# USB_Hub.net
KiCad netlist of a schematic drawn in Altium Designer
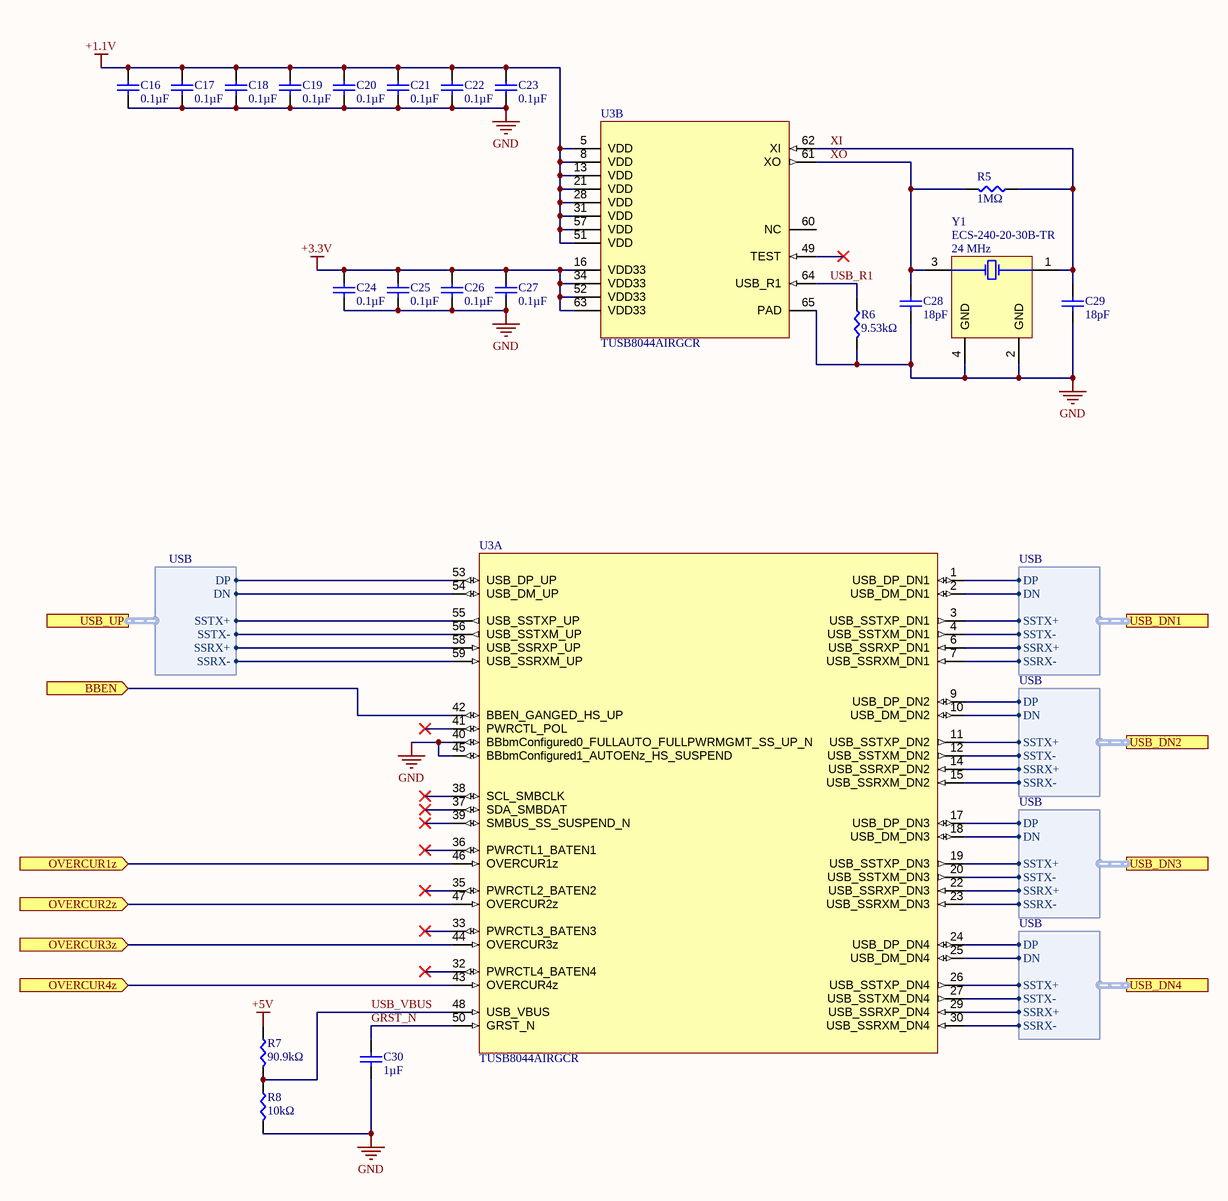
[diagram p0: USB_Hub.SchDoc]

(export (version "E")
  (design (tool "Eeschema 10.0.6"))
  (components
    (comp (ref "C16")
      (value "0.1µF")
      (footprint "CAP0402")
      (description "0.1 µF ±10% 50V Ceramic Capacitor X5R 0402 (1005 Metric)")
      (fields (field (name "VOLTAGE") "50V") (field (name "Comment") "CC0402KRX5R9BB104"))
      (libsource (lib "Schlib1") (part "CC0402KRX5R9BB104"))
    )
    (comp (ref "C17")
      (value "0.1µF")
      (footprint "CAP0402")
      (description "0.1 µF ±10% 50V Ceramic Capacitor X5R 0402 (1005 Metric)")
      (fields (field (name "VOLTAGE") "50V") (field (name "Comment") "CC0402KRX5R9BB104"))
      (libsource (lib "Schlib1") (part "CC0402KRX5R9BB104"))
    )
    (comp (ref "C18")
      (value "0.1µF")
      (footprint "CAP0402")
      (description "0.1 µF ±10% 50V Ceramic Capacitor X5R 0402 (1005 Metric)")
      (fields (field (name "VOLTAGE") "50V") (field (name "Comment") "CC0402KRX5R9BB104"))
      (libsource (lib "Schlib1") (part "CC0402KRX5R9BB104"))
    )
    (comp (ref "C19")
      (value "0.1µF")
      (footprint "CAP0402")
      (description "0.1 µF ±10% 50V Ceramic Capacitor X5R 0402 (1005 Metric)")
      (fields (field (name "VOLTAGE") "50V") (field (name "Comment") "CC0402KRX5R9BB104"))
      (libsource (lib "Schlib1") (part "CC0402KRX5R9BB104"))
    )
    (comp (ref "C20")
      (value "0.1µF")
      (footprint "CAP0402")
      (description "0.1 µF ±10% 50V Ceramic Capacitor X5R 0402 (1005 Metric)")
      (fields (field (name "VOLTAGE") "50V") (field (name "Comment") "CC0402KRX5R9BB104"))
      (libsource (lib "Schlib1") (part "CC0402KRX5R9BB104"))
    )
    (comp (ref "C21")
      (value "0.1µF")
      (footprint "CAP0402")
      (description "0.1 µF ±10% 50V Ceramic Capacitor X5R 0402 (1005 Metric)")
      (fields (field (name "VOLTAGE") "50V") (field (name "Comment") "CC0402KRX5R9BB104"))
      (libsource (lib "Schlib1") (part "CC0402KRX5R9BB104"))
    )
    (comp (ref "C22")
      (value "0.1µF")
      (footprint "CAP0402")
      (description "0.1 µF ±10% 50V Ceramic Capacitor X5R 0402 (1005 Metric)")
      (fields (field (name "VOLTAGE") "50V") (field (name "Comment") "CC0402KRX5R9BB104"))
      (libsource (lib "Schlib1") (part "CC0402KRX5R9BB104"))
    )
    (comp (ref "C23")
      (value "0.1µF")
      (footprint "CAP0402")
      (description "0.1 µF ±10% 50V Ceramic Capacitor X5R 0402 (1005 Metric)")
      (fields (field (name "VOLTAGE") "50V") (field (name "Comment") "CC0402KRX5R9BB104"))
      (libsource (lib "Schlib1") (part "CC0402KRX5R9BB104"))
    )
    (comp (ref "C24")
      (value "0.1µF")
      (footprint "CAP0402")
      (description "0.1 µF ±10% 50V Ceramic Capacitor X5R 0402 (1005 Metric)")
      (fields (field (name "VOLTAGE") "50V") (field (name "Comment") "CC0402KRX5R9BB104"))
      (libsource (lib "Schlib1") (part "CC0402KRX5R9BB104"))
    )
    (comp (ref "C25")
      (value "0.1µF")
      (footprint "CAP0402")
      (description "0.1 µF ±10% 50V Ceramic Capacitor X5R 0402 (1005 Metric)")
      (fields (field (name "VOLTAGE") "50V") (field (name "Comment") "CC0402KRX5R9BB104"))
      (libsource (lib "Schlib1") (part "CC0402KRX5R9BB104"))
    )
    (comp (ref "C26")
      (value "0.1µF")
      (footprint "CAP0402")
      (description "0.1 µF ±10% 50V Ceramic Capacitor X5R 0402 (1005 Metric)")
      (fields (field (name "VOLTAGE") "50V") (field (name "Comment") "CC0402KRX5R9BB104"))
      (libsource (lib "Schlib1") (part "CC0402KRX5R9BB104"))
    )
    (comp (ref "C27")
      (value "0.1µF")
      (footprint "CAP0402")
      (description "0.1 µF ±10% 50V Ceramic Capacitor X5R 0402 (1005 Metric)")
      (fields (field (name "VOLTAGE") "50V") (field (name "Comment") "CC0402KRX5R9BB104"))
      (libsource (lib "Schlib1") (part "CC0402KRX5R9BB104"))
    )
    (comp (ref "C28")
      (value "18pF")
      (footprint "CAP0402")
      (description "18 pF ±1% 50V Ceramic Capacitor C0G, NP0 0402 (1005 Metric)")
      (fields (field (name "VOLTAGE") "50V") (field (name "Comment") "GJM1555C1H180FB01D"))
      (libsource (lib "Schlib1") (part "GJM1555C1H180FB01D"))
    )
    (comp (ref "C29")
      (value "18pF")
      (footprint "CAP0402")
      (description "18 pF ±1% 50V Ceramic Capacitor C0G, NP0 0402 (1005 Metric)")
      (fields (field (name "VOLTAGE") "50V") (field (name "Comment") "GJM1555C1H180FB01D"))
      (libsource (lib "Schlib1") (part "GJM1555C1H180FB01D"))
    )
    (comp (ref "C30")
      (value "1µF")
      (footprint "CAP0402")
      (description "1 µF ±10% 50V Ceramic Capacitor X5R 0402 (1005 Metric)")
      (fields (field (name "VOLTAGE") "50V") (field (name "Comment") "GRM155R61H105KE05D"))
      (libsource (lib "Schlib1") (part "GRM155R61H105KE05D"))
    )
    (comp (ref "R5")
      (value "1MΩ")
      (footprint "RES0402")
      (description "1 MOhms ±1% 0.063W, 1/16W Chip Resistor 0402 (1005 Metric) Moisture Resistant Thick Film")
      (fields (field (name "Comment") "RC0402FR-071ML"))
      (libsource (lib "Schlib1") (part "RC0402FR-071ML"))
    )
    (comp (ref "R6")
      (value "9.53kΩ")
      (footprint "RES0402")
      (description "9.53 kOhms ±1% 0.1W, 1/10W Chip Resistor 0402 (1005 Metric) Automotive AEC-Q200 Thick Film")
      (fields (field (name "Comment") "CRCW04029K53FKED"))
      (libsource (lib "Schlib1") (part "CRCW04029K53FKED"))
    )
    (comp (ref "R7")
      (value "90.9kΩ")
      (footprint "RES0402")
      (description "90.9 kOhms ±1% 0.063W, 1/16W Chip Resistor 0402 (1005 Metric) Moisture Resistant Thick Film")
      (fields (field (name "Comment") "RC0402FR-0790K9L"))
      (libsource (lib "Schlib1") (part "RC0402FR-0790K9L"))
    )
    (comp (ref "R8")
      (value "10kΩ")
      (footprint "RES0402")
      (description "10 kOhms ±1% 0.063W, 1/16W Chip Resistor 0402 (1005 Metric) Moisture Resistant Thick Film")
      (fields (field (name "Comment") "RC0402FR-0710KL"))
      (libsource (lib "Schlib1") (part "RC0402FR-0710KL"))
    )
    (comp (ref "U3")
      (value "TUSB8044AIRGCR")
      (footprint "RGC0064G")
      (description "Four-port USB 3.2 x1 Gen1 hub with USB billboard 64-VQFN -40 to 85")
      (fields (field (name "COPYRIGHT") "Copyright (C) 2026 Ultra Librarian. All rights reserved."))
      (libsource (lib "Schlib1") (part "TUSB8044AIRGCR"))
    )
    (comp (ref "Y1")
      (value "ECS-240-20-30B-TR")
      (footprint "ECS-240-20-30B-TR")
      (description "24 MHz ±30ppm Crystal 20pF 30 Ohms 4-SMD, No Lead")
      (fields (field (name "ALTIUM_VALUE") "24 MHz"))
      (libsource (lib "Schlib1") (part "ECS-240-20-30B-TR"))
    )
  )
  (nets
    (net (code "2") (name "+1.1V") (class "Default")
      (node (ref "C16") (pin "2") (pinfunction "2_2") (pintype "passive"))
      (node (ref "C17") (pin "2") (pinfunction "2_2") (pintype "passive"))
      (node (ref "C18") (pin "2") (pinfunction "2_2") (pintype "passive"))
      (node (ref "C19") (pin "2") (pinfunction "2_2") (pintype "passive"))
      (node (ref "C20") (pin "2") (pinfunction "2_2") (pintype "passive"))
      (node (ref "C21") (pin "2") (pinfunction "2_2") (pintype "passive"))
      (node (ref "C22") (pin "2") (pinfunction "2_2") (pintype "passive"))
      (node (ref "C23") (pin "2") (pinfunction "2_2") (pintype "passive"))
      (node (ref "U3") (pin "13") (pinfunction "VDD_13") (pintype "power_in"))
      (node (ref "U3") (pin "21") (pinfunction "VDD_21") (pintype "power_in"))
      (node (ref "U3") (pin "28") (pinfunction "VDD_28") (pintype "power_in"))
      (node (ref "U3") (pin "31") (pinfunction "VDD_31") (pintype "power_in"))
      (node (ref "U3") (pin "5") (pinfunction "VDD_5") (pintype "power_in"))
      (node (ref "U3") (pin "51") (pinfunction "VDD_51") (pintype "power_in"))
      (node (ref "U3") (pin "57") (pinfunction "VDD_57") (pintype "power_in"))
      (node (ref "U3") (pin "8") (pinfunction "VDD_8") (pintype "power_in"))
    )
    (net (code "3") (name "+3.3V") (class "Default")
      (node (ref "C24") (pin "2") (pinfunction "2_2") (pintype "passive"))
      (node (ref "C25") (pin "2") (pinfunction "2_2") (pintype "passive"))
      (node (ref "C26") (pin "2") (pinfunction "2_2") (pintype "passive"))
      (node (ref "C27") (pin "2") (pinfunction "2_2") (pintype "passive"))
      (node (ref "U3") (pin "16") (pinfunction "VDD33_16") (pintype "power_in"))
      (node (ref "U3") (pin "34") (pinfunction "VDD33_34") (pintype "power_in"))
      (node (ref "U3") (pin "52") (pinfunction "VDD33_52") (pintype "power_in"))
      (node (ref "U3") (pin "63") (pinfunction "VDD33_63") (pintype "power_in"))
    )
    (net (code "4") (name "+5V") (class "Default")
      (node (ref "R7") (pin "2") (pinfunction "2_2") (pintype "passive"))
    )
    (net (code "5") (name "/BBEN") (class "Default")
      (node (ref "U3") (pin "42") (pinfunction "BBEN_GANGED_HS_UP_42") (pintype "bidirectional"))
    )
    (net (code "6") (name "/GRST_N") (class "Default")
      (node (ref "C30") (pin "2") (pinfunction "2_2") (pintype "passive"))
      (node (ref "U3") (pin "50") (pinfunction "GRST_N_50") (pintype "input"))
    )
    (net (code "7") (name "/OVERCUR1z") (class "Default")
      (node (ref "U3") (pin "46") (pinfunction "OVERCUR1z_46") (pintype "input"))
    )
    (net (code "8") (name "/OVERCUR2z") (class "Default")
      (node (ref "U3") (pin "47") (pinfunction "OVERCUR2z_47") (pintype "input"))
    )
    (net (code "9") (name "/OVERCUR3z") (class "Default")
      (node (ref "U3") (pin "44") (pinfunction "OVERCUR3z_44") (pintype "input"))
    )
    (net (code "10") (name "/OVERCUR4z") (class "Default")
      (node (ref "U3") (pin "43") (pinfunction "OVERCUR4z_43") (pintype "input"))
    )
    (net (code "11") (name "/USB_R1") (class "Default")
      (node (ref "R6") (pin "2") (pinfunction "2_2") (pintype "passive"))
      (node (ref "U3") (pin "64") (pinfunction "USB_R1_64") (pintype "input"))
    )
    (net (code "12") (name "/USB_VBUS") (class "Default")
      (node (ref "R7") (pin "1") (pinfunction "1_1") (pintype "passive"))
      (node (ref "R8") (pin "2") (pinfunction "2_2") (pintype "passive"))
      (node (ref "U3") (pin "48") (pinfunction "USB_VBUS_48") (pintype "input"))
    )
    (net (code "13") (name "/XI") (class "Default")
      (node (ref "C29") (pin "2") (pinfunction "2_2") (pintype "passive"))
      (node (ref "R5") (pin "2") (pinfunction "2_2") (pintype "passive"))
      (node (ref "U3") (pin "62") (pinfunction "XI_62") (pintype "input"))
      (node (ref "Y1") (pin "1") (pintype "passive"))
    )
    (net (code "14") (name "/XO") (class "Default")
      (node (ref "C28") (pin "2") (pinfunction "2_2") (pintype "passive"))
      (node (ref "R5") (pin "1") (pinfunction "1_1") (pintype "passive"))
      (node (ref "U3") (pin "61") (pinfunction "XO_61") (pintype "output"))
      (node (ref "Y1") (pin "3") (pintype "passive"))
    )
    (net (code "16") (name "GND") (class "Default")
      (node (ref "C16") (pin "1") (pinfunction "1_1") (pintype "passive"))
      (node (ref "C17") (pin "1") (pinfunction "1_1") (pintype "passive"))
      (node (ref "C18") (pin "1") (pinfunction "1_1") (pintype "passive"))
      (node (ref "C19") (pin "1") (pinfunction "1_1") (pintype "passive"))
      (node (ref "C20") (pin "1") (pinfunction "1_1") (pintype "passive"))
      (node (ref "C21") (pin "1") (pinfunction "1_1") (pintype "passive"))
      (node (ref "C22") (pin "1") (pinfunction "1_1") (pintype "passive"))
      (node (ref "C23") (pin "1") (pinfunction "1_1") (pintype "passive"))
      (node (ref "C24") (pin "1") (pinfunction "1_1") (pintype "passive"))
      (node (ref "C25") (pin "1") (pinfunction "1_1") (pintype "passive"))
      (node (ref "C26") (pin "1") (pinfunction "1_1") (pintype "passive"))
      (node (ref "C27") (pin "1") (pinfunction "1_1") (pintype "passive"))
      (node (ref "C28") (pin "1") (pinfunction "1_1") (pintype "passive"))
      (node (ref "C29") (pin "1") (pinfunction "1_1") (pintype "passive"))
      (node (ref "C30") (pin "1") (pinfunction "1_1") (pintype "passive"))
      (node (ref "R6") (pin "1") (pinfunction "1_1") (pintype "passive"))
      (node (ref "R8") (pin "1") (pinfunction "1_1") (pintype "passive"))
      (node (ref "U3") (pin "40") (pinfunction "BBbmConfigured0_FULLAUTO_FULLPWRMGMT_SS_UP_N_40") (pintype "bidirectional"))
      (node (ref "U3") (pin "45") (pinfunction "BBbmConfigured1_AUTOENz_HS_SUSPEND_45") (pintype "bidirectional"))
      (node (ref "U3") (pin "65") (pinfunction "PAD_65") (pintype "passive"))
      (node (ref "Y1") (pin "2") (pinfunction "GND_2") (pintype "passive"))
      (node (ref "Y1") (pin "4") (pinfunction "GND_4") (pintype "passive"))
    )
    (net (code "17") (name "unconnected-(U3A-PWRCTL1_BATEN1-Pad36)") (class "Default")
      (node (ref "U3") (pin "36") (pinfunction "PWRCTL1_BATEN1_36") (pintype "bidirectional+no_connect"))
    )
    (net (code "18") (name "unconnected-(U3A-PWRCTL2_BATEN2-Pad35)") (class "Default")
      (node (ref "U3") (pin "35") (pinfunction "PWRCTL2_BATEN2_35") (pintype "bidirectional+no_connect"))
    )
    (net (code "19") (name "unconnected-(U3A-PWRCTL3_BATEN3-Pad33)") (class "Default")
      (node (ref "U3") (pin "33") (pinfunction "PWRCTL3_BATEN3_33") (pintype "bidirectional+no_connect"))
    )
    (net (code "20") (name "unconnected-(U3A-PWRCTL4_BATEN4-Pad32)") (class "Default")
      (node (ref "U3") (pin "32") (pinfunction "PWRCTL4_BATEN4_32") (pintype "bidirectional+no_connect"))
    )
    (net (code "21") (name "unconnected-(U3A-PWRCTL_POL-Pad41)") (class "Default")
      (node (ref "U3") (pin "41") (pinfunction "PWRCTL_POL_41") (pintype "bidirectional+no_connect"))
    )
    (net (code "22") (name "unconnected-(U3A-SCL_SMBCLK-Pad38)") (class "Default")
      (node (ref "U3") (pin "38") (pinfunction "SCL_SMBCLK_38") (pintype "bidirectional+no_connect"))
    )
    (net (code "23") (name "unconnected-(U3A-SDA_SMBDAT-Pad37)") (class "Default")
      (node (ref "U3") (pin "37") (pinfunction "SDA_SMBDAT_37") (pintype "bidirectional+no_connect"))
    )
    (net (code "24") (name "unconnected-(U3A-SMBUS_SS_SUSPEND_N-Pad39)") (class "Default")
      (node (ref "U3") (pin "39") (pinfunction "SMBUS_SS_SUSPEND_N_39") (pintype "bidirectional+no_connect"))
    )
    (net (code "25") (name "unconnected-(U3A-USB_DM_DN1-Pad2)") (class "Default")
      (node (ref "U3") (pin "2") (pinfunction "USB_DM_DN1_2") (pintype "bidirectional"))
    )
    (net (code "26") (name "unconnected-(U3A-USB_DM_DN2-Pad10)") (class "Default")
      (node (ref "U3") (pin "10") (pinfunction "USB_DM_DN2_10") (pintype "bidirectional"))
    )
    (net (code "27") (name "unconnected-(U3A-USB_DM_DN3-Pad18)") (class "Default")
      (node (ref "U3") (pin "18") (pinfunction "USB_DM_DN3_18") (pintype "bidirectional"))
    )
    (net (code "28") (name "unconnected-(U3A-USB_DM_DN4-Pad25)") (class "Default")
      (node (ref "U3") (pin "25") (pinfunction "USB_DM_DN4_25") (pintype "bidirectional"))
    )
    (net (code "29") (name "unconnected-(U3A-USB_DM_UP-Pad54)") (class "Default")
      (node (ref "U3") (pin "54") (pinfunction "USB_DM_UP_54") (pintype "bidirectional"))
    )
    (net (code "30") (name "unconnected-(U3A-USB_DP_DN1-Pad1)") (class "Default")
      (node (ref "U3") (pin "1") (pinfunction "USB_DP_DN1_1") (pintype "bidirectional"))
    )
    (net (code "31") (name "unconnected-(U3A-USB_DP_DN2-Pad9)") (class "Default")
      (node (ref "U3") (pin "9") (pinfunction "USB_DP_DN2_9") (pintype "bidirectional"))
    )
    (net (code "32") (name "unconnected-(U3A-USB_DP_DN3-Pad17)") (class "Default")
      (node (ref "U3") (pin "17") (pinfunction "USB_DP_DN3_17") (pintype "bidirectional"))
    )
    (net (code "33") (name "unconnected-(U3A-USB_DP_DN4-Pad24)") (class "Default")
      (node (ref "U3") (pin "24") (pinfunction "USB_DP_DN4_24") (pintype "bidirectional"))
    )
    (net (code "34") (name "unconnected-(U3A-USB_DP_UP-Pad53)") (class "Default")
      (node (ref "U3") (pin "53") (pinfunction "USB_DP_UP_53") (pintype "bidirectional"))
    )
    (net (code "35") (name "unconnected-(U3A-USB_SSRXM_DN1-Pad7)") (class "Default")
      (node (ref "U3") (pin "7") (pinfunction "USB_SSRXM_DN1_7") (pintype "input"))
    )
    (net (code "36") (name "unconnected-(U3A-USB_SSRXM_DN2-Pad15)") (class "Default")
      (node (ref "U3") (pin "15") (pinfunction "USB_SSRXM_DN2_15") (pintype "input"))
    )
    (net (code "37") (name "unconnected-(U3A-USB_SSRXM_DN3-Pad23)") (class "Default")
      (node (ref "U3") (pin "23") (pinfunction "USB_SSRXM_DN3_23") (pintype "input"))
    )
    (net (code "38") (name "unconnected-(U3A-USB_SSRXM_DN4-Pad30)") (class "Default")
      (node (ref "U3") (pin "30") (pinfunction "USB_SSRXM_DN4_30") (pintype "input"))
    )
    (net (code "39") (name "unconnected-(U3A-USB_SSRXM_UP-Pad59)") (class "Default")
      (node (ref "U3") (pin "59") (pinfunction "USB_SSRXM_UP_59") (pintype "input"))
    )
    (net (code "40") (name "unconnected-(U3A-USB_SSRXP_DN1-Pad6)") (class "Default")
      (node (ref "U3") (pin "6") (pinfunction "USB_SSRXP_DN1_6") (pintype "input"))
    )
    (net (code "41") (name "unconnected-(U3A-USB_SSRXP_DN2-Pad14)") (class "Default")
      (node (ref "U3") (pin "14") (pinfunction "USB_SSRXP_DN2_14") (pintype "input"))
    )
    (net (code "42") (name "unconnected-(U3A-USB_SSRXP_DN3-Pad22)") (class "Default")
      (node (ref "U3") (pin "22") (pinfunction "USB_SSRXP_DN3_22") (pintype "input"))
    )
    (net (code "43") (name "unconnected-(U3A-USB_SSRXP_DN4-Pad29)") (class "Default")
      (node (ref "U3") (pin "29") (pinfunction "USB_SSRXP_DN4_29") (pintype "input"))
    )
    (net (code "44") (name "unconnected-(U3A-USB_SSRXP_UP-Pad58)") (class "Default")
      (node (ref "U3") (pin "58") (pinfunction "USB_SSRXP_UP_58") (pintype "input"))
    )
    (net (code "45") (name "unconnected-(U3A-USB_SSTXM_DN1-Pad4)") (class "Default")
      (node (ref "U3") (pin "4") (pinfunction "USB_SSTXM_DN1_4") (pintype "output"))
    )
    (net (code "46") (name "unconnected-(U3A-USB_SSTXM_DN2-Pad12)") (class "Default")
      (node (ref "U3") (pin "12") (pinfunction "USB_SSTXM_DN2_12") (pintype "output"))
    )
    (net (code "47") (name "unconnected-(U3A-USB_SSTXM_DN3-Pad20)") (class "Default")
      (node (ref "U3") (pin "20") (pinfunction "USB_SSTXM_DN3_20") (pintype "output"))
    )
    (net (code "48") (name "unconnected-(U3A-USB_SSTXM_DN4-Pad27)") (class "Default")
      (node (ref "U3") (pin "27") (pinfunction "USB_SSTXM_DN4_27") (pintype "output"))
    )
    (net (code "49") (name "unconnected-(U3A-USB_SSTXM_UP-Pad56)") (class "Default")
      (node (ref "U3") (pin "56") (pinfunction "USB_SSTXM_UP_56") (pintype "output"))
    )
    (net (code "50") (name "unconnected-(U3A-USB_SSTXP_DN1-Pad3)") (class "Default")
      (node (ref "U3") (pin "3") (pinfunction "USB_SSTXP_DN1_3") (pintype "output"))
    )
    (net (code "51") (name "unconnected-(U3A-USB_SSTXP_DN2-Pad11)") (class "Default")
      (node (ref "U3") (pin "11") (pinfunction "USB_SSTXP_DN2_11") (pintype "output"))
    )
    (net (code "52") (name "unconnected-(U3A-USB_SSTXP_DN3-Pad19)") (class "Default")
      (node (ref "U3") (pin "19") (pinfunction "USB_SSTXP_DN3_19") (pintype "output"))
    )
    (net (code "53") (name "unconnected-(U3A-USB_SSTXP_DN4-Pad26)") (class "Default")
      (node (ref "U3") (pin "26") (pinfunction "USB_SSTXP_DN4_26") (pintype "output"))
    )
    (net (code "54") (name "unconnected-(U3A-USB_SSTXP_UP-Pad55)") (class "Default")
      (node (ref "U3") (pin "55") (pinfunction "USB_SSTXP_UP_55") (pintype "output"))
    )
    (net (code "55") (name "unconnected-(U3B-NC-Pad60)") (class "Default")
      (node (ref "U3") (pin "60") (pinfunction "NC_60") (pintype "passive"))
    )
    (net (code "56") (name "unconnected-(U3B-TEST-Pad49)") (class "Default")
      (node (ref "U3") (pin "49") (pinfunction "TEST_49") (pintype "input+no_connect"))
    )
  )
)
